# FUSE_AND_VI_SENSE.net
KiCad netlist of a schematic drawn in Altium Designer
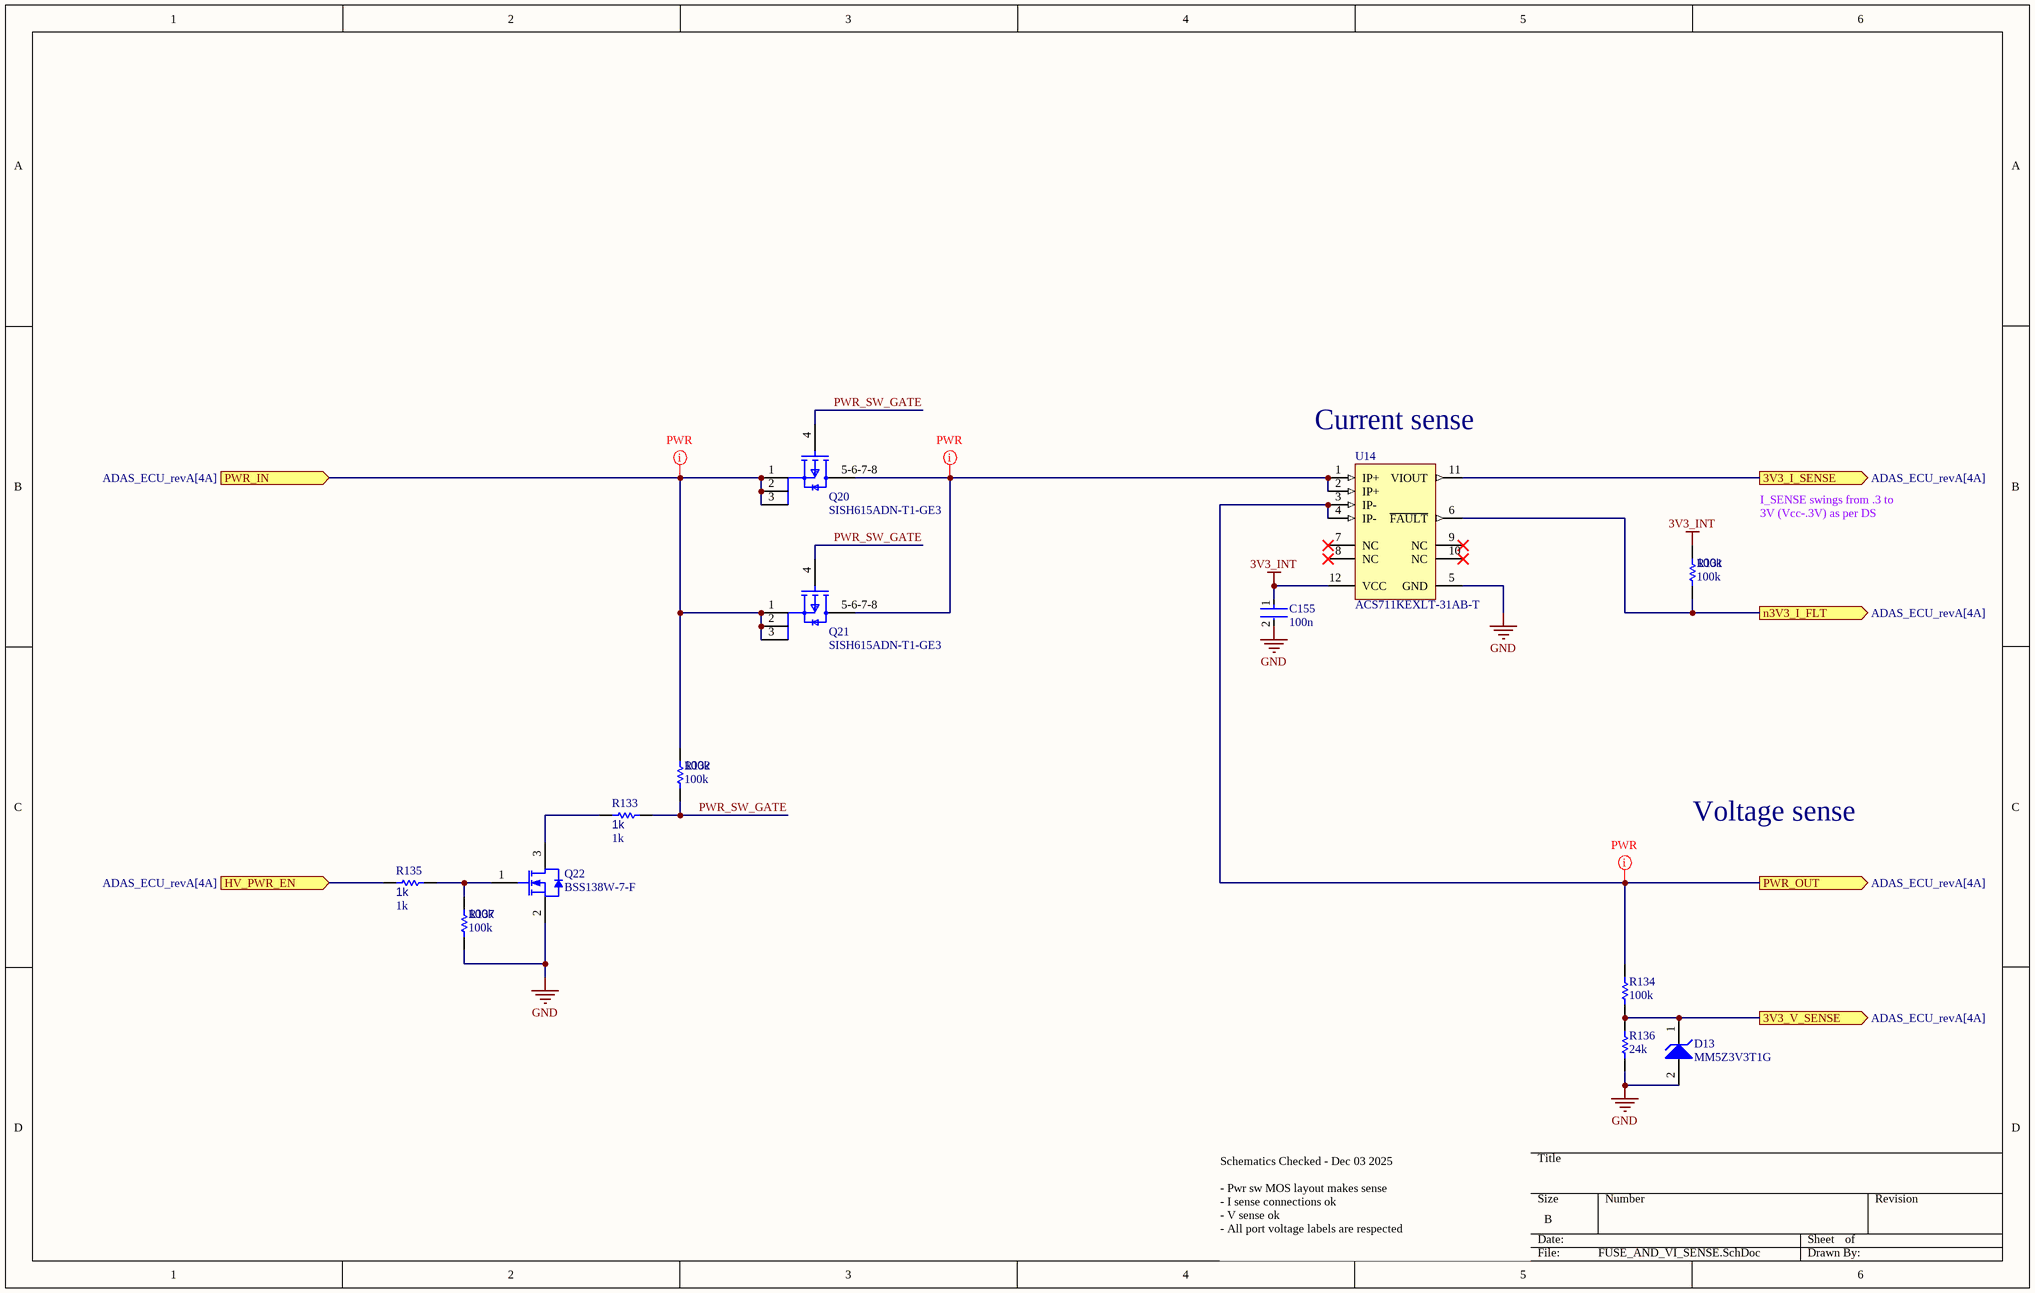
[diagram p0: FUSE_AND_VI_SENSE.SchDoc]

(export (version "E")
  (design (tool "Eeschema 10.0.6"))
  (components
    (comp (ref "C155")
      (value "100n")
      (footprint "FP-0402-L_1_0_0_05-W_0_5-IPC_A")
      (description "LARGE PADS, 0402 CAP, CHANGE COMMENT TO MATCH REAL P/N")
      (libsource (lib "Space Concordia") (part "b4654b650e69147ec39a6b967a45e02"))
    )
    (comp (ref "D13")
      (value "MM5Z3V3T1G")
      (footprint "ONSC-SOD-523-2-502-01_V")
      (description "Zener Voltage Regulator, 500 mW, 2-Pin SOD-523, Pb-Free, Tape and Reel")
      (fields (field (name "MANUFACTURER") "On Semiconductor"))
      (libsource (lib "Altium Content Vault") (part "ONSC-K1A2-2"))
    )
    (comp (ref "Q20")
      (value "SISH615ADN-T1-GE3")
      (footprint "SISH615ADN-T1-GE3-Footprint-1")
      (description "Trans MOSFET P-CH 20V 22.1A 8-Pin PowerPAK 1212 EP T/R")
      (libsource (lib "Space Concordia") (part "CMP-013-00036-4"))
    )
    (comp (ref "Q21")
      (value "SISH615ADN-T1-GE3")
      (footprint "SISH615ADN-T1-GE3-Footprint-1")
      (description "Trans MOSFET P-CH 20V 22.1A 8-Pin PowerPAK 1212 EP T/R")
      (libsource (lib "Space Concordia") (part "CMP-013-00036-4"))
    )
    (comp (ref "Q22")
      (value "BSS138W-7-F")
      (footprint "DIOD-SOT323-3_V")
      (fields (field (name "MANUFACTURER") "DiodesIncorporated"))
      (libsource (lib "Altium Content Vault") (part "NEMOS-GSD-3"))
    )
    (comp (ref "R131")
      (value "100k")
      (footprint "R0603B")
      (description "Resistor")
      (fields (field (name "ALTIUM_VALUE") "100k"))
      (libsource (lib "Space Concordia") (part "Resistor"))
    )
    (comp (ref "R132")
      (value "100k")
      (footprint "R0603B")
      (description "Resistor")
      (fields (field (name "ALTIUM_VALUE") "100k"))
      (libsource (lib "Space Concordia") (part "Resistor"))
    )
    (comp (ref "R133")
      (value "1k")
      (footprint "R0603B")
      (description "Resistor")
      (fields (field (name "ALTIUM_VALUE") "1k"))
      (libsource (lib "Space Concordia") (part "Resistor"))
    )
    (comp (ref "R134")
      (value "100k")
      (footprint "R0603B")
      (description "Resistor")
      (libsource (lib "Space Concordia") (part "Resistor"))
    )
    (comp (ref "R135")
      (value "1k")
      (footprint "R0603B")
      (description "Resistor")
      (fields (field (name "ALTIUM_VALUE") "1k"))
      (libsource (lib "Space Concordia") (part "Resistor"))
    )
    (comp (ref "R136")
      (value "24k")
      (footprint "R0603B")
      (description "Resistor")
      (libsource (lib "Space Concordia") (part "Resistor"))
    )
    (comp (ref "R137")
      (value "100k")
      (footprint "R0603B")
      (description "Resistor")
      (fields (field (name "ALTIUM_VALUE") "100k"))
      (libsource (lib "Space Concordia") (part "Resistor"))
    )
    (comp (ref "U14")
      (value "ACS711KEXLT-31AB-T")
      (footprint "ALEG-EX-12_V")
      (libsource (lib "Altium Content Vault") (part "ALEG-ACS711-QFN-12"))
    )
  )
  (nets
    (net (code "1") (name "/3V3_I_SENSE") (class "Default")
      (node (ref "U14") (pin "11") (pinfunction "VIOUT_11") (pintype "output"))
    )
    (net (code "2") (name "/3V3_V_SENSE") (class "Default")
      (node (ref "D13") (pin "1") (pinfunction "K_1") (pintype "passive"))
      (node (ref "R134") (pin "1") (pinfunction "1_1") (pintype "passive"))
      (node (ref "R136") (pin "2") (pinfunction "2_2") (pintype "passive"))
    )
    (net (code "3") (name "/HV_PWR_EN") (class "Default")
      (node (ref "R135") (pin "1") (pinfunction "1_1") (pintype "passive"))
    )
    (net (code "4") (name "/PWR_IN") (class "Default")
      (node (ref "Q20") (pin "1") (pinfunction "S_1") (pintype "passive"))
      (node (ref "Q20") (pin "2") (pinfunction "S_2") (pintype "passive"))
      (node (ref "Q20") (pin "3") (pinfunction "S_3") (pintype "passive"))
      (node (ref "Q21") (pin "1") (pinfunction "S_1") (pintype "passive"))
      (node (ref "Q21") (pin "2") (pinfunction "S_2") (pintype "passive"))
      (node (ref "Q21") (pin "3") (pinfunction "S_3") (pintype "passive"))
      (node (ref "R132") (pin "2") (pinfunction "2_2") (pintype "passive"))
    )
    (net (code "5") (name "/PWR_OUT") (class "Default")
      (node (ref "R134") (pin "2") (pinfunction "2_2") (pintype "passive"))
      (node (ref "U14") (pin "3") (pinfunction "IP-_3") (pintype "input"))
      (node (ref "U14") (pin "4") (pinfunction "IP-_4") (pintype "input"))
    )
    (net (code "6") (name "/PWR_SW_GATE") (class "Default")
      (node (ref "Q20") (pin "4") (pinfunction "G_4") (pintype "passive"))
      (node (ref "Q21") (pin "4") (pinfunction "G_4") (pintype "passive"))
      (node (ref "R132") (pin "1") (pinfunction "1_1") (pintype "passive"))
      (node (ref "R133") (pin "2") (pinfunction "2_2") (pintype "passive"))
    )
    (net (code "7") (name "/n3V3_I_FLT") (class "Default")
      (node (ref "R131") (pin "1") (pinfunction "1_1") (pintype "passive"))
      (node (ref "U14") (pin "6") (pinfunction "~{FAULT}_6") (pintype "output"))
    )
    (net (code "8") (name "3V3_INT") (class "Default")
      (node (ref "C155") (pin "1") (pinfunction "1_1") (pintype "passive"))
      (node (ref "R131") (pin "2") (pinfunction "2_2") (pintype "passive"))
      (node (ref "U14") (pin "12") (pinfunction "VCC_12") (pintype "power_in"))
    )
    (net (code "9") (name "GND") (class "Default")
      (node (ref "C155") (pin "2") (pinfunction "2_2") (pintype "passive"))
      (node (ref "D13") (pin "2") (pinfunction "A_2") (pintype "passive"))
      (node (ref "Q22") (pin "2") (pinfunction "S_2") (pintype "passive"))
      (node (ref "R136") (pin "1") (pinfunction "1_1") (pintype "passive"))
      (node (ref "R137") (pin "1") (pinfunction "1_1") (pintype "passive"))
      (node (ref "U14") (pin "5") (pinfunction "GND_5") (pintype "power_in"))
    )
    (net (code "10") (name "Net-(Q20-D)") (class "Default")
      (node (ref "Q20") (pin "5-6-7-8") (pinfunction "D_5-6-7-8") (pintype "passive"))
      (node (ref "Q21") (pin "5-6-7-8") (pinfunction "D_5-6-7-8") (pintype "passive"))
      (node (ref "U14") (pin "1") (pinfunction "IP+_1") (pintype "input"))
      (node (ref "U14") (pin "2") (pinfunction "IP+_2") (pintype "input"))
    )
    (net (code "11") (name "Net-(Q22-D)") (class "Default")
      (node (ref "Q22") (pin "3") (pinfunction "D_3") (pintype "passive"))
      (node (ref "R133") (pin "1") (pinfunction "1_1") (pintype "passive"))
    )
    (net (code "12") (name "Net-(Q22-G)") (class "Default")
      (node (ref "Q22") (pin "1") (pinfunction "G_1") (pintype "passive"))
      (node (ref "R135") (pin "2") (pinfunction "2_2") (pintype "passive"))
      (node (ref "R137") (pin "2") (pinfunction "2_2") (pintype "passive"))
    )
    (net (code "13") (name "unconnected-(U14-NC-Pad7)") (class "Default")
      (node (ref "U14") (pin "7") (pinfunction "NC_7") (pintype "passive+no_connect"))
    )
    (net (code "14") (name "unconnected-(U14-NC-Pad8)") (class "Default")
      (node (ref "U14") (pin "8") (pinfunction "NC_8") (pintype "passive+no_connect"))
    )
    (net (code "15") (name "unconnected-(U14-NC-Pad9)") (class "Default")
      (node (ref "U14") (pin "9") (pinfunction "NC_9") (pintype "passive+no_connect"))
    )
    (net (code "16") (name "unconnected-(U14-NC-Pad10)") (class "Default")
      (node (ref "U14") (pin "10") (pinfunction "NC_10") (pintype "passive+no_connect"))
    )
  )
)
